# Station_lithobius_motenio_usb.net
KiCad netlist of a schematic drawn in EAGLE
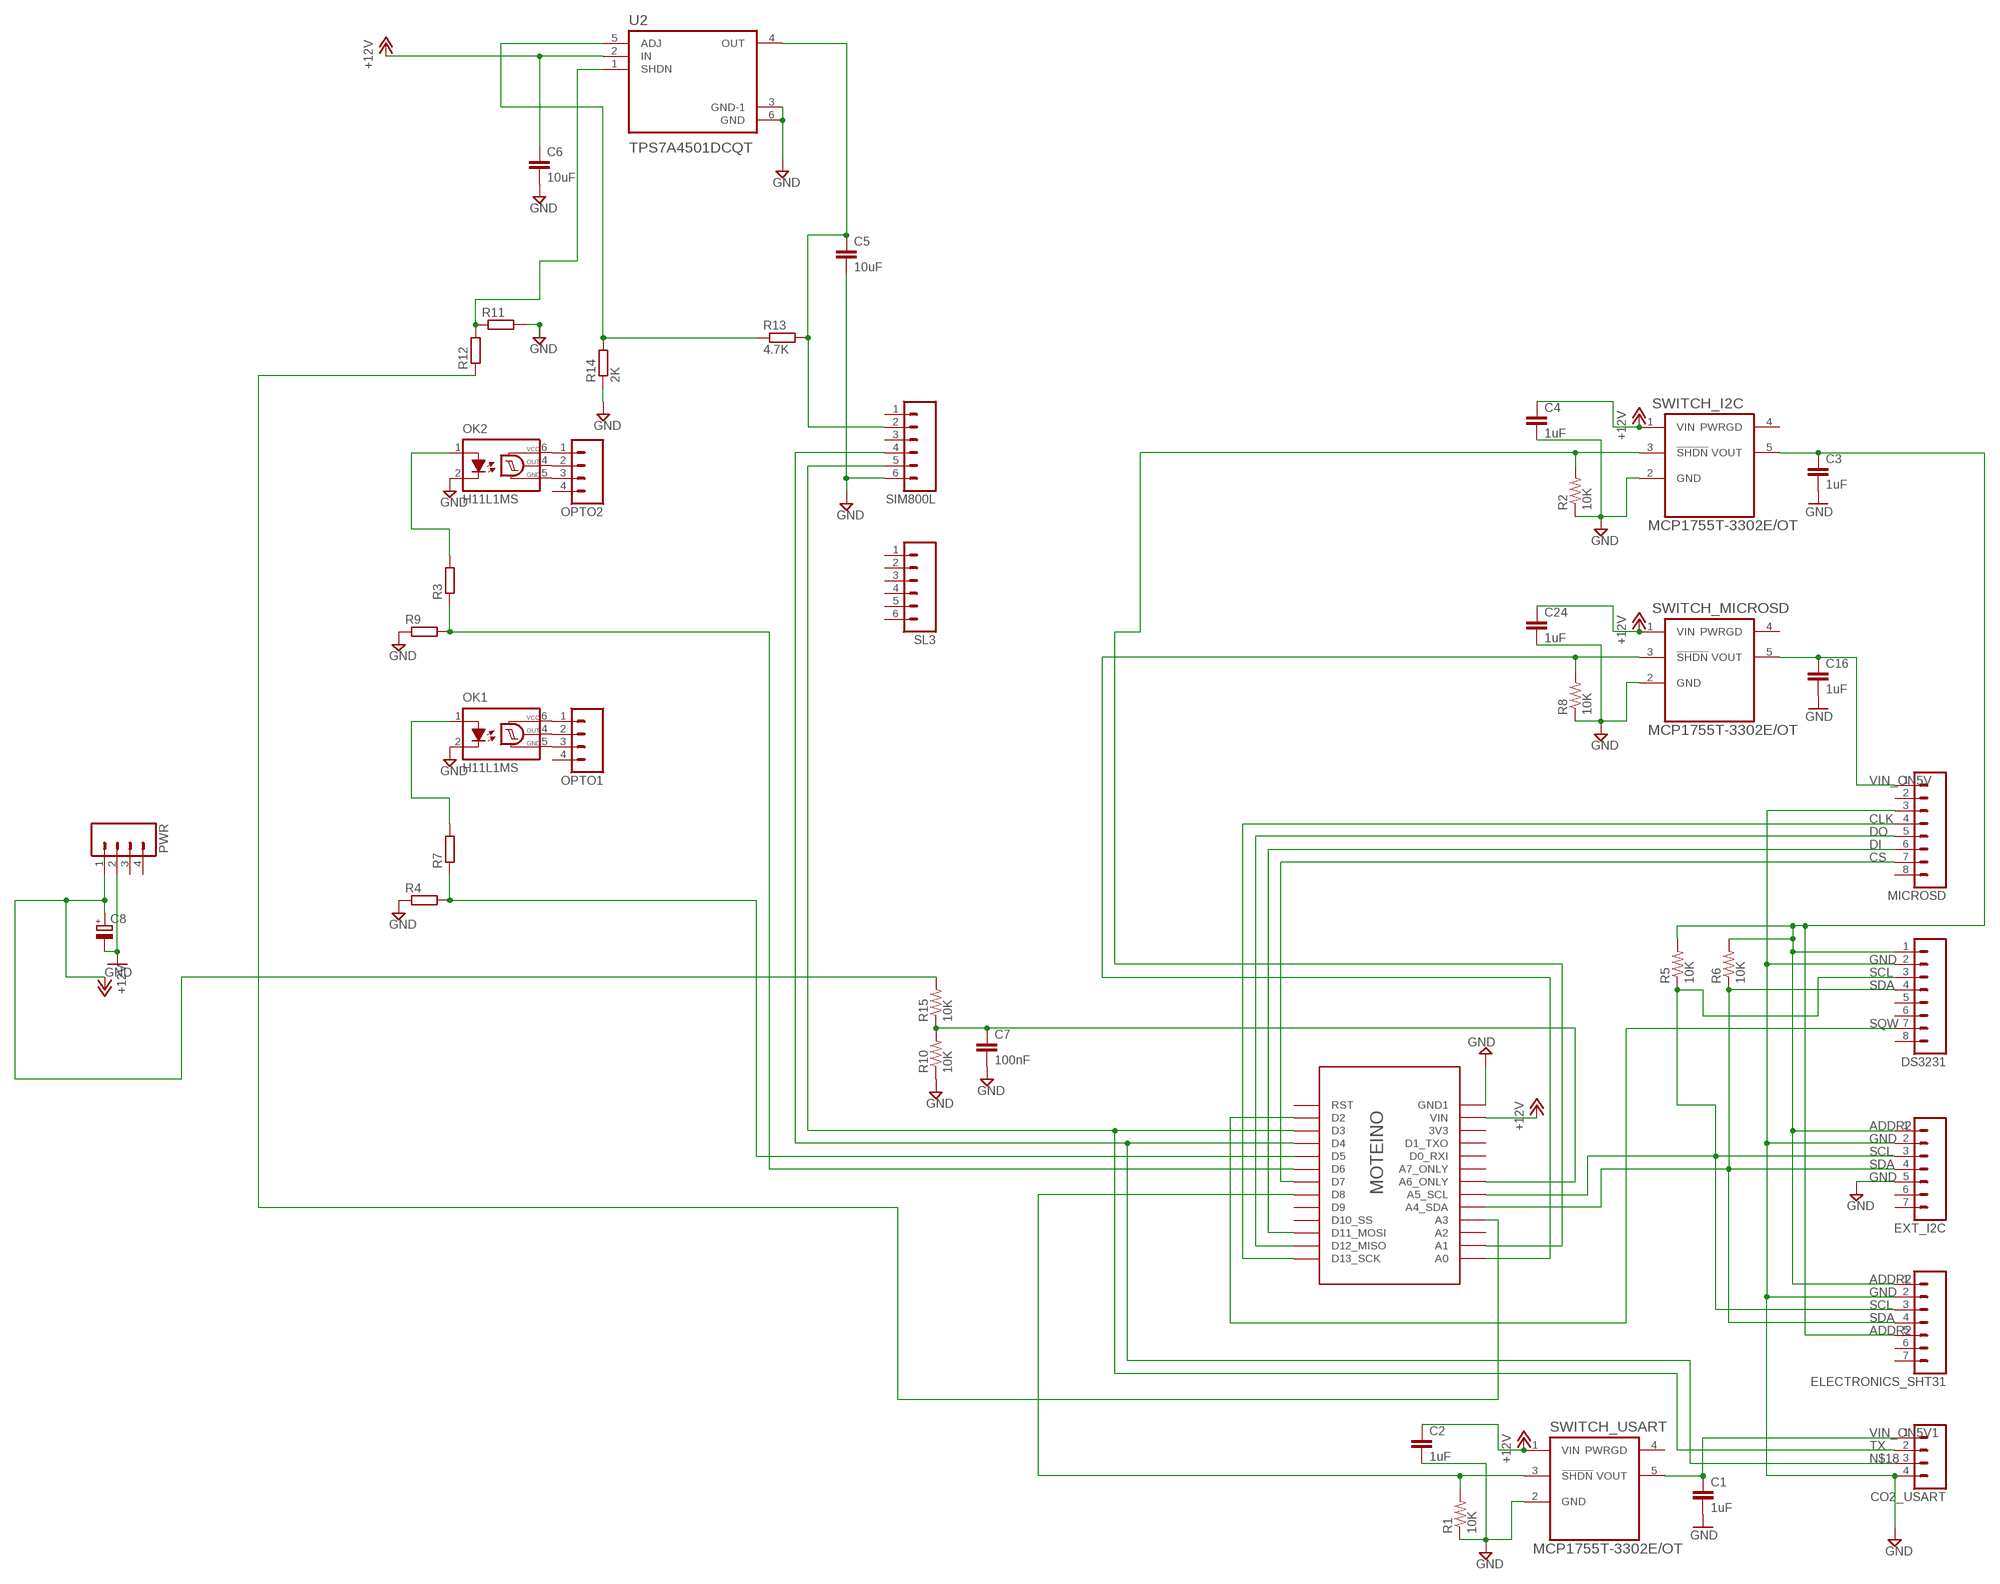
[diagram p0: schematic, sheet 1]

(export (version "E")
  (design (tool "Eeschema 10.0.6"))
  (components
    (comp (ref "C1")
      (value "1uF")
      (footprint "eagle-import:C0805K")
      (libsource (lib "eagle-import") (part "C-EUC0805K"))
    )
    (comp (ref "C2")
      (value "1uF")
      (footprint "eagle-import:C0805K")
      (libsource (lib "eagle-import") (part "C-EUC0805K"))
    )
    (comp (ref "C3")
      (value "1uF")
      (footprint "eagle-import:C0805K")
      (libsource (lib "eagle-import") (part "C-EUC0805K"))
    )
    (comp (ref "C4")
      (value "1uF")
      (footprint "eagle-import:C0805K")
      (libsource (lib "eagle-import") (part "C-EUC0805K"))
    )
    (comp (ref "C5")
      (value "10uF")
      (footprint "eagle-import:C0805K")
      (libsource (lib "eagle-import") (part "C-EUC0805K"))
    )
    (comp (ref "C6")
      (value "10uF")
      (footprint "eagle-import:C0805K")
      (libsource (lib "eagle-import") (part "C-EUC0805K"))
    )
    (comp (ref "C7")
      (value "100nF")
      (footprint "eagle-import:C0805K")
      (libsource (lib "eagle-import") (part "C-EUC0805K"))
    )
    (comp (ref "C8")
      (value "CPOL-EU153CLV-0810")
      (footprint "eagle-import:153CLV-0810")
      (libsource (lib "eagle-import") (part "CPOL-EU153CLV-0810"))
    )
    (comp (ref "C16")
      (value "1uF")
      (footprint "eagle-import:C0805K")
      (libsource (lib "eagle-import") (part "C-EUC0805K"))
    )
    (comp (ref "C24")
      (value "1uF")
      (footprint "eagle-import:C0805K")
      (libsource (lib "eagle-import") (part "C-EUC0805K"))
    )
    (comp (ref "CO2_USART")
      (value "M04")
      (footprint "eagle-import:04P")
      (libsource (lib "eagle-import") (part "M04"))
    )
    (comp (ref "DS3231")
      (value "M08")
      (footprint "eagle-import:08P")
      (libsource (lib "eagle-import") (part "M08"))
    )
    (comp (ref "ELECTRONICS_SHT31")
      (value "M07")
      (footprint "eagle-import:07P")
      (libsource (lib "eagle-import") (part "M07"))
    )
    (comp (ref "EXT_I2C")
      (value "M07")
      (footprint "eagle-import:07P")
      (libsource (lib "eagle-import") (part "M07"))
    )
    (comp (ref "MICROSD")
      (value "M08")
      (footprint "eagle-import:08P")
      (libsource (lib "eagle-import") (part "M08"))
    )
    (comp (ref "OK1")
      (value "H11L1MS")
      (footprint "eagle-import:DIL6-SMD")
      (libsource (lib "eagle-import") (part "H11LMS1"))
    )
    (comp (ref "OK2")
      (value "H11L1MS")
      (footprint "eagle-import:DIL6-SMD")
      (libsource (lib "eagle-import") (part "H11LMS1"))
    )
    (comp (ref "OPTO1")
      (value "M04")
      (footprint "eagle-import:04P")
      (libsource (lib "eagle-import") (part "M04"))
    )
    (comp (ref "OPTO2")
      (value "M04")
      (footprint "eagle-import:04P")
      (libsource (lib "eagle-import") (part "M04"))
    )
    (comp (ref "PWR")
      (value "M04")
      (footprint "eagle-import:04P")
      (libsource (lib "eagle-import") (part "M04"))
    )
    (comp (ref "R1")
      (value "10K")
      (footprint "eagle-import:R2012W")
      (libsource (lib "eagle-import") (part "R-US_R2012W"))
    )
    (comp (ref "R2")
      (value "10K")
      (footprint "eagle-import:R2012W")
      (libsource (lib "eagle-import") (part "R-US_R2012W"))
    )
    (comp (ref "R3")
      (value "R-EU_R0805")
      (footprint "eagle-import:R0805")
      (libsource (lib "eagle-import") (part "R-EU_R0805"))
    )
    (comp (ref "R4")
      (value "R-EU_R0805")
      (footprint "eagle-import:R0805")
      (libsource (lib "eagle-import") (part "R-EU_R0805"))
    )
    (comp (ref "R5")
      (value "10K")
      (footprint "eagle-import:R2012W")
      (libsource (lib "eagle-import") (part "R-US_R2012W"))
    )
    (comp (ref "R6")
      (value "10K")
      (footprint "eagle-import:R2012W")
      (libsource (lib "eagle-import") (part "R-US_R2012W"))
    )
    (comp (ref "R7")
      (value "R-EU_R0805")
      (footprint "eagle-import:R0805")
      (libsource (lib "eagle-import") (part "R-EU_R0805"))
    )
    (comp (ref "R8")
      (value "10K")
      (footprint "eagle-import:R2012W")
      (libsource (lib "eagle-import") (part "R-US_R2012W"))
    )
    (comp (ref "R9")
      (value "R-EU_R0805")
      (footprint "eagle-import:R0805")
      (libsource (lib "eagle-import") (part "R-EU_R0805"))
    )
    (comp (ref "R10")
      (value "10K")
      (footprint "eagle-import:R2012W")
      (libsource (lib "eagle-import") (part "R-US_R2012W"))
    )
    (comp (ref "R11")
      (value "R-EU_R0805")
      (footprint "eagle-import:R0805")
      (libsource (lib "eagle-import") (part "R-EU_R0805"))
    )
    (comp (ref "R12")
      (value "R-EU_R0805")
      (footprint "eagle-import:R0805")
      (libsource (lib "eagle-import") (part "R-EU_R0805"))
    )
    (comp (ref "R13")
      (value "4.7K")
      (footprint "eagle-import:R0805")
      (libsource (lib "eagle-import") (part "R-EU_R0805"))
    )
    (comp (ref "R14")
      (value "2K")
      (footprint "eagle-import:R0805")
      (libsource (lib "eagle-import") (part "R-EU_R0805"))
    )
    (comp (ref "R15")
      (value "10K")
      (footprint "eagle-import:R2012W")
      (libsource (lib "eagle-import") (part "R-US_R2012W"))
    )
    (comp (ref "SIM800L")
      (value "M06")
      (footprint "eagle-import:06P")
      (libsource (lib "eagle-import") (part "M06"))
    )
    (comp (ref "SL3")
      (value "M06")
      (footprint "eagle-import:06P")
      (libsource (lib "eagle-import") (part "M06"))
    )
    (comp (ref "SWITCH_I2C")
      (value "MCP1755T-3302E/OT")
      (footprint "eagle-import:SOT95P270X145-5N")
      (libsource (lib "eagle-import") (part "MCP1755T-3302E/OT"))
    )
    (comp (ref "SWITCH_MICROSD")
      (value "MCP1755T-3302E/OT")
      (footprint "eagle-import:SOT95P270X145-5N")
      (libsource (lib "eagle-import") (part "MCP1755T-3302E/OT"))
    )
    (comp (ref "SWITCH_USART")
      (value "MCP1755T-3302E/OT")
      (footprint "eagle-import:SOT95P270X145-5N")
      (libsource (lib "eagle-import") (part "MCP1755T-3302E/OT"))
    )
    (comp (ref "U$1")
      (value "MOTEINO_SIMPLE")
      (footprint "eagle-import:MOTEINO_SIMPLE")
      (libsource (lib "eagle-import") (part "MOTEINO_SIMPLE"))
    )
    (comp (ref "U2")
      (value "TPS7A4501DCQT")
      (footprint "eagle-import:SOT127P706X180-6N")
      (fields (field (name "MF") "Texas Instruments"))
      (libsource (lib "eagle-import") (part "TPS7A4501DCQT"))
    )
  )
  (nets
    (net (code "1") (name "+12V") (class "Default")
      (node (ref "C2") (pin "1") (pinfunction "1_1") (pintype "passive"))
      (node (ref "C24") (pin "1") (pinfunction "1_1") (pintype "passive"))
      (node (ref "C4") (pin "1") (pinfunction "1_1") (pintype "passive"))
      (node (ref "C6") (pin "1") (pinfunction "1_1") (pintype "passive"))
      (node (ref "C8") (pin "+") (pinfunction "+_+") (pintype "passive"))
      (node (ref "PWR") (pin "1") (pinfunction "1_1") (pintype "passive"))
      (node (ref "R15") (pin "2") (pinfunction "2_2") (pintype "passive"))
      (node (ref "SWITCH_I2C") (pin "1") (pinfunction "VIN_1") (pintype "power_in"))
      (node (ref "SWITCH_MICROSD") (pin "1") (pinfunction "VIN_1") (pintype "power_in"))
      (node (ref "SWITCH_USART") (pin "1") (pinfunction "VIN_1") (pintype "power_in"))
      (node (ref "U$1") (pin "VIN") (pinfunction "VIN_VIN") (pintype "bidirectional"))
      (node (ref "U2") (pin "2") (pinfunction "IN_2") (pintype "input"))
    )
    (net (code "2") (name "/ADDR2") (class "Default")
      (node (ref "C3") (pin "1") (pinfunction "1_1") (pintype "passive"))
      (node (ref "DS3231") (pin "1") (pinfunction "1_1") (pintype "passive"))
      (node (ref "ELECTRONICS_SHT31") (pin "1") (pinfunction "1_1") (pintype "passive"))
      (node (ref "ELECTRONICS_SHT31") (pin "5") (pinfunction "5_5") (pintype "passive"))
      (node (ref "EXT_I2C") (pin "1") (pinfunction "1_1") (pintype "passive"))
      (node (ref "R5") (pin "2") (pinfunction "2_2") (pintype "passive"))
      (node (ref "R6") (pin "2") (pinfunction "2_2") (pintype "passive"))
      (node (ref "SWITCH_I2C") (pin "5") (pinfunction "VOUT_5") (pintype "output"))
    )
    (net (code "3") (name "/CLK") (class "Default")
      (node (ref "MICROSD") (pin "4") (pinfunction "4_4") (pintype "passive"))
      (node (ref "U$1") (pin "D13_SCK") (pinfunction "D13_SCK_D13_SCK") (pintype "bidirectional"))
    )
    (net (code "4") (name "/CS") (class "Default")
      (node (ref "MICROSD") (pin "7") (pinfunction "7_7") (pintype "passive"))
      (node (ref "U$1") (pin "D7") (pinfunction "D7_D7") (pintype "bidirectional"))
    )
    (net (code "5") (name "/DI") (class "Default")
      (node (ref "MICROSD") (pin "6") (pinfunction "6_6") (pintype "passive"))
      (node (ref "U$1") (pin "D11_MOSI") (pinfunction "D11_MOSI_D11_MOSI") (pintype "bidirectional"))
    )
    (net (code "6") (name "/DO") (class "Default")
      (node (ref "MICROSD") (pin "5") (pinfunction "5_5") (pintype "passive"))
      (node (ref "U$1") (pin "D12_MISO") (pinfunction "D12_MISO_D12_MISO") (pintype "bidirectional"))
    )
    (net (code "7") (name "/N$18") (class "Default")
      (node (ref "CO2_USART") (pin "3") (pinfunction "3_3") (pintype "passive"))
      (node (ref "SIM800L") (pin "4") (pinfunction "4_4") (pintype "passive"))
      (node (ref "U$1") (pin "D4") (pinfunction "D4_D4") (pintype "bidirectional"))
    )
    (net (code "8") (name "/SCL") (class "Default")
      (node (ref "DS3231") (pin "3") (pinfunction "3_3") (pintype "passive"))
      (node (ref "ELECTRONICS_SHT31") (pin "3") (pinfunction "3_3") (pintype "passive"))
      (node (ref "EXT_I2C") (pin "3") (pinfunction "3_3") (pintype "passive"))
      (node (ref "R5") (pin "1") (pinfunction "1_1") (pintype "passive"))
      (node (ref "U$1") (pin "A5_SCL") (pinfunction "A5_SCL_A5_SCL") (pintype "bidirectional"))
    )
    (net (code "9") (name "/SDA") (class "Default")
      (node (ref "DS3231") (pin "4") (pinfunction "4_4") (pintype "passive"))
      (node (ref "ELECTRONICS_SHT31") (pin "4") (pinfunction "4_4") (pintype "passive"))
      (node (ref "EXT_I2C") (pin "4") (pinfunction "4_4") (pintype "passive"))
      (node (ref "R6") (pin "1") (pinfunction "1_1") (pintype "passive"))
      (node (ref "U$1") (pin "A4_SDA") (pinfunction "A4_SDA_A4_SDA") (pintype "bidirectional"))
    )
    (net (code "10") (name "/SQW") (class "Default")
      (node (ref "DS3231") (pin "7") (pinfunction "7_7") (pintype "passive"))
      (node (ref "U$1") (pin "D2") (pinfunction "D2_D2") (pintype "bidirectional"))
    )
    (net (code "11") (name "/TX") (class "Default")
      (node (ref "CO2_USART") (pin "2") (pinfunction "2_2") (pintype "passive"))
      (node (ref "SIM800L") (pin "5") (pinfunction "5_5") (pintype "passive"))
      (node (ref "U$1") (pin "D3") (pinfunction "D3_D3") (pintype "bidirectional"))
    )
    (net (code "12") (name "/VIN_ON5V") (class "Default")
      (node (ref "C16") (pin "1") (pinfunction "1_1") (pintype "passive"))
      (node (ref "MICROSD") (pin "1") (pinfunction "1_1") (pintype "passive"))
      (node (ref "SWITCH_MICROSD") (pin "5") (pinfunction "VOUT_5") (pintype "output"))
    )
    (net (code "13") (name "/VIN_ON5V1") (class "Default")
      (node (ref "C1") (pin "1") (pinfunction "1_1") (pintype "passive"))
      (node (ref "CO2_USART") (pin "1") (pinfunction "1_1") (pintype "passive"))
      (node (ref "SWITCH_USART") (pin "5") (pinfunction "VOUT_5") (pintype "output"))
    )
    (net (code "14") (name "GND") (class "Default")
      (node (ref "C1") (pin "2") (pinfunction "2_2") (pintype "passive"))
      (node (ref "C16") (pin "2") (pinfunction "2_2") (pintype "passive"))
      (node (ref "C2") (pin "2") (pinfunction "2_2") (pintype "passive"))
      (node (ref "C24") (pin "2") (pinfunction "2_2") (pintype "passive"))
      (node (ref "C3") (pin "2") (pinfunction "2_2") (pintype "passive"))
      (node (ref "C4") (pin "2") (pinfunction "2_2") (pintype "passive"))
      (node (ref "C5") (pin "2") (pinfunction "2_2") (pintype "passive"))
      (node (ref "C6") (pin "2") (pinfunction "2_2") (pintype "passive"))
      (node (ref "C7") (pin "2") (pinfunction "2_2") (pintype "passive"))
      (node (ref "C8") (pin "-") (pinfunction "-_-") (pintype "passive"))
      (node (ref "CO2_USART") (pin "4") (pinfunction "4_4") (pintype "passive"))
      (node (ref "DS3231") (pin "2") (pinfunction "2_2") (pintype "passive"))
      (node (ref "ELECTRONICS_SHT31") (pin "2") (pinfunction "2_2") (pintype "passive"))
      (node (ref "EXT_I2C") (pin "2") (pinfunction "2_2") (pintype "passive"))
      (node (ref "EXT_I2C") (pin "5") (pinfunction "5_5") (pintype "passive"))
      (node (ref "MICROSD") (pin "3") (pinfunction "3_3") (pintype "passive"))
      (node (ref "OK1") (pin "2") (pinfunction "C_2") (pintype "passive"))
      (node (ref "OK2") (pin "2") (pinfunction "C_2") (pintype "passive"))
      (node (ref "PWR") (pin "2") (pinfunction "2_2") (pintype "passive"))
      (node (ref "R1") (pin "1") (pinfunction "1_1") (pintype "passive"))
      (node (ref "R10") (pin "1") (pinfunction "1_1") (pintype "passive"))
      (node (ref "R11") (pin "2") (pinfunction "2_2") (pintype "passive"))
      (node (ref "R14") (pin "1") (pinfunction "1_1") (pintype "passive"))
      (node (ref "R2") (pin "1") (pinfunction "1_1") (pintype "passive"))
      (node (ref "R4") (pin "1") (pinfunction "1_1") (pintype "passive"))
      (node (ref "R8") (pin "1") (pinfunction "1_1") (pintype "passive"))
      (node (ref "R9") (pin "1") (pinfunction "1_1") (pintype "passive"))
      (node (ref "SIM800L") (pin "6") (pinfunction "6_6") (pintype "passive"))
      (node (ref "SWITCH_I2C") (pin "2") (pinfunction "GND_2") (pintype "passive"))
      (node (ref "SWITCH_MICROSD") (pin "2") (pinfunction "GND_2") (pintype "passive"))
      (node (ref "SWITCH_USART") (pin "2") (pinfunction "GND_2") (pintype "passive"))
      (node (ref "U$1") (pin "GND1") (pinfunction "GND1_GND1") (pintype "bidirectional"))
      (node (ref "U2") (pin "3") (pinfunction "GND-1_3") (pintype "power_in"))
      (node (ref "U2") (pin "6") (pinfunction "GND_6") (pintype "power_in"))
    )
    (net (code "15") (name "Net-(C7-Pad1)") (class "Default")
      (node (ref "C7") (pin "1") (pinfunction "1_1") (pintype "passive"))
      (node (ref "R10") (pin "2") (pinfunction "2_2") (pintype "passive"))
      (node (ref "R15") (pin "1") (pinfunction "1_1") (pintype "passive"))
      (node (ref "U$1") (pin "A6_ONLY") (pinfunction "A6_ONLY_A6_ONLY") (pintype "bidirectional"))
    )
    (net (code "16") (name "Net-(OK1-A)") (class "Default")
      (node (ref "OK1") (pin "1") (pinfunction "A_1") (pintype "passive"))
      (node (ref "R7") (pin "2") (pinfunction "2_2") (pintype "passive"))
    )
    (net (code "17") (name "Net-(OK1-GND)") (class "Default")
      (node (ref "OK1") (pin "5") (pinfunction "GND_5") (pintype "power_in"))
      (node (ref "OPTO1") (pin "3") (pinfunction "3_3") (pintype "passive"))
    )
    (net (code "18") (name "Net-(OK1-OUT)") (class "Default")
      (node (ref "OK1") (pin "4") (pinfunction "OUT_4") (pintype "output"))
      (node (ref "OPTO1") (pin "2") (pinfunction "2_2") (pintype "passive"))
    )
    (net (code "19") (name "Net-(OK1-VCC)") (class "Default")
      (node (ref "OK1") (pin "6") (pinfunction "VCC_6") (pintype "power_in"))
      (node (ref "OPTO1") (pin "1") (pinfunction "1_1") (pintype "passive"))
    )
    (net (code "20") (name "Net-(OK2-A)") (class "Default")
      (node (ref "OK2") (pin "1") (pinfunction "A_1") (pintype "passive"))
      (node (ref "R3") (pin "2") (pinfunction "2_2") (pintype "passive"))
    )
    (net (code "21") (name "Net-(OK2-GND)") (class "Default")
      (node (ref "OK2") (pin "5") (pinfunction "GND_5") (pintype "power_in"))
      (node (ref "OPTO2") (pin "3") (pinfunction "3_3") (pintype "passive"))
    )
    (net (code "22") (name "Net-(OK2-OUT)") (class "Default")
      (node (ref "OK2") (pin "4") (pinfunction "OUT_4") (pintype "output"))
      (node (ref "OPTO2") (pin "2") (pinfunction "2_2") (pintype "passive"))
    )
    (net (code "23") (name "Net-(OK2-VCC)") (class "Default")
      (node (ref "OK2") (pin "6") (pinfunction "VCC_6") (pintype "power_in"))
      (node (ref "OPTO2") (pin "1") (pinfunction "1_1") (pintype "passive"))
    )
    (net (code "24") (name "Net-(R3-Pad1)") (class "Default")
      (node (ref "R3") (pin "1") (pinfunction "1_1") (pintype "passive"))
      (node (ref "R9") (pin "2") (pinfunction "2_2") (pintype "passive"))
      (node (ref "U$1") (pin "D6") (pinfunction "D6_D6") (pintype "bidirectional"))
    )
    (net (code "25") (name "Net-(R4-Pad2)") (class "Default")
      (node (ref "R4") (pin "2") (pinfunction "2_2") (pintype "passive"))
      (node (ref "R7") (pin "1") (pinfunction "1_1") (pintype "passive"))
      (node (ref "U$1") (pin "D5") (pinfunction "D5_D5") (pintype "bidirectional"))
    )
    (net (code "26") (name "Net-(R12-Pad1)") (class "Default")
      (node (ref "R12") (pin "1") (pinfunction "1_1") (pintype "passive"))
      (node (ref "U$1") (pin "A3") (pinfunction "A3_A3") (pintype "bidirectional"))
    )
    (net (code "27") (name "Net-(SWITCH_I2C-~{SHDN})") (class "Default")
      (node (ref "R2") (pin "2") (pinfunction "2_2") (pintype "passive"))
      (node (ref "SWITCH_I2C") (pin "3") (pinfunction "~{SHDN}_3") (pintype "input"))
      (node (ref "U$1") (pin "A1") (pinfunction "A1_A1") (pintype "bidirectional"))
    )
    (net (code "28") (name "Net-(SWITCH_MICROSD-~{SHDN})") (class "Default")
      (node (ref "R8") (pin "2") (pinfunction "2_2") (pintype "passive"))
      (node (ref "SWITCH_MICROSD") (pin "3") (pinfunction "~{SHDN}_3") (pintype "input"))
      (node (ref "U$1") (pin "A0") (pinfunction "A0_A0") (pintype "bidirectional"))
    )
    (net (code "29") (name "Net-(SWITCH_USART-~{SHDN})") (class "Default")
      (node (ref "R1") (pin "2") (pinfunction "2_2") (pintype "passive"))
      (node (ref "SWITCH_USART") (pin "3") (pinfunction "~{SHDN}_3") (pintype "input"))
      (node (ref "U$1") (pin "D8") (pinfunction "D8_D8") (pintype "bidirectional"))
    )
    (net (code "30") (name "Net-(U2-ADJ)") (class "Default")
      (node (ref "R13") (pin "1") (pinfunction "1_1") (pintype "passive"))
      (node (ref "R14") (pin "2") (pinfunction "2_2") (pintype "passive"))
      (node (ref "U2") (pin "5") (pinfunction "ADJ_5") (pintype "input"))
    )
    (net (code "31") (name "Net-(U2-OUT)") (class "Default")
      (node (ref "C5") (pin "1") (pinfunction "1_1") (pintype "passive"))
      (node (ref "R13") (pin "2") (pinfunction "2_2") (pintype "passive"))
      (node (ref "SIM800L") (pin "2") (pinfunction "2_2") (pintype "passive"))
      (node (ref "U2") (pin "4") (pinfunction "OUT_4") (pintype "output"))
    )
    (net (code "32") (name "Net-(U2-SHDN)") (class "Default")
      (node (ref "R11") (pin "1") (pinfunction "1_1") (pintype "passive"))
      (node (ref "R12") (pin "2") (pinfunction "2_2") (pintype "passive"))
      (node (ref "U2") (pin "1") (pinfunction "SHDN_1") (pintype "input"))
    )
    (net (code "33") (name "unconnected-(DS3231-Pad5)") (class "Default")
      (node (ref "DS3231") (pin "5") (pinfunction "5_5") (pintype "passive"))
    )
    (net (code "34") (name "unconnected-(DS3231-Pad6)") (class "Default")
      (node (ref "DS3231") (pin "6") (pinfunction "6_6") (pintype "passive"))
    )
    (net (code "35") (name "unconnected-(DS3231-Pad8)") (class "Default")
      (node (ref "DS3231") (pin "8") (pinfunction "8_8") (pintype "passive"))
    )
    (net (code "36") (name "unconnected-(ELECTRONICS_SHT31-Pad6)") (class "Default")
      (node (ref "ELECTRONICS_SHT31") (pin "6") (pinfunction "6_6") (pintype "passive"))
    )
    (net (code "37") (name "unconnected-(ELECTRONICS_SHT31-Pad7)") (class "Default")
      (node (ref "ELECTRONICS_SHT31") (pin "7") (pinfunction "7_7") (pintype "passive"))
    )
    (net (code "38") (name "unconnected-(EXT_I2C-Pad6)") (class "Default")
      (node (ref "EXT_I2C") (pin "6") (pinfunction "6_6") (pintype "passive"))
    )
    (net (code "39") (name "unconnected-(EXT_I2C-Pad7)") (class "Default")
      (node (ref "EXT_I2C") (pin "7") (pinfunction "7_7") (pintype "passive"))
    )
    (net (code "40") (name "unconnected-(MICROSD-Pad2)") (class "Default")
      (node (ref "MICROSD") (pin "2") (pinfunction "2_2") (pintype "passive"))
    )
    (net (code "41") (name "unconnected-(MICROSD-Pad8)") (class "Default")
      (node (ref "MICROSD") (pin "8") (pinfunction "8_8") (pintype "passive"))
    )
    (net (code "42") (name "unconnected-(OPTO1-Pad4)") (class "Default")
      (node (ref "OPTO1") (pin "4") (pinfunction "4_4") (pintype "passive"))
    )
    (net (code "43") (name "unconnected-(OPTO2-Pad4)") (class "Default")
      (node (ref "OPTO2") (pin "4") (pinfunction "4_4") (pintype "passive"))
    )
    (net (code "44") (name "unconnected-(PWR-Pad3)") (class "Default")
      (node (ref "PWR") (pin "3") (pinfunction "3_3") (pintype "passive"))
    )
    (net (code "45") (name "unconnected-(PWR-Pad4)") (class "Default")
      (node (ref "PWR") (pin "4") (pinfunction "4_4") (pintype "passive"))
    )
    (net (code "46") (name "unconnected-(SIM800L-Pad1)") (class "Default")
      (node (ref "SIM800L") (pin "1") (pinfunction "1_1") (pintype "passive"))
    )
    (net (code "47") (name "unconnected-(SIM800L-Pad3)") (class "Default")
      (node (ref "SIM800L") (pin "3") (pinfunction "3_3") (pintype "passive"))
    )
    (net (code "48") (name "unconnected-(SL3-Pad1)") (class "Default")
      (node (ref "SL3") (pin "1") (pinfunction "1_1") (pintype "passive"))
    )
    (net (code "49") (name "unconnected-(SL3-Pad2)") (class "Default")
      (node (ref "SL3") (pin "2") (pinfunction "2_2") (pintype "passive"))
    )
    (net (code "50") (name "unconnected-(SL3-Pad3)") (class "Default")
      (node (ref "SL3") (pin "3") (pinfunction "3_3") (pintype "passive"))
    )
    (net (code "51") (name "unconnected-(SL3-Pad4)") (class "Default")
      (node (ref "SL3") (pin "4") (pinfunction "4_4") (pintype "passive"))
    )
    (net (code "52") (name "unconnected-(SL3-Pad5)") (class "Default")
      (node (ref "SL3") (pin "5") (pinfunction "5_5") (pintype "passive"))
    )
    (net (code "53") (name "unconnected-(SL3-Pad6)") (class "Default")
      (node (ref "SL3") (pin "6") (pinfunction "6_6") (pintype "passive"))
    )
    (net (code "54") (name "unconnected-(SWITCH_I2C-PWRGD-Pad4)") (class "Default")
      (node (ref "SWITCH_I2C") (pin "4") (pinfunction "PWRGD_4") (pintype "output"))
    )
    (net (code "55") (name "unconnected-(SWITCH_MICROSD-PWRGD-Pad4)") (class "Default")
      (node (ref "SWITCH_MICROSD") (pin "4") (pinfunction "PWRGD_4") (pintype "output"))
    )
    (net (code "56") (name "unconnected-(SWITCH_USART-PWRGD-Pad4)") (class "Default")
      (node (ref "SWITCH_USART") (pin "4") (pinfunction "PWRGD_4") (pintype "output"))
    )
    (net (code "57") (name "unconnected-(U$1-Pad3V3)") (class "Default")
      (node (ref "U$1") (pin "3V3") (pinfunction "3V3_3V3") (pintype "bidirectional"))
    )
    (net (code "58") (name "unconnected-(U$1-PadA2)") (class "Default")
      (node (ref "U$1") (pin "A2") (pinfunction "A2_A2") (pintype "bidirectional"))
    )
    (net (code "59") (name "unconnected-(U$1-PadA7_ONLY)") (class "Default")
      (node (ref "U$1") (pin "A7_ONLY") (pinfunction "A7_ONLY_A7_ONLY") (pintype "bidirectional"))
    )
    (net (code "60") (name "unconnected-(U$1-PadD0_RXI)") (class "Default")
      (node (ref "U$1") (pin "D0_RXI") (pinfunction "D0_RXI_D0_RXI") (pintype "bidirectional"))
    )
    (net (code "61") (name "unconnected-(U$1-PadD1_TXO)") (class "Default")
      (node (ref "U$1") (pin "D1_TXO") (pinfunction "D1_TXO_D1_TXO") (pintype "bidirectional"))
    )
    (net (code "62") (name "unconnected-(U$1-PadD9)") (class "Default")
      (node (ref "U$1") (pin "D9") (pinfunction "D9_D9") (pintype "bidirectional"))
    )
    (net (code "63") (name "unconnected-(U$1-PadD10_SS)") (class "Default")
      (node (ref "U$1") (pin "D10_SS") (pinfunction "D10_SS_D10_SS") (pintype "bidirectional"))
    )
    (net (code "64") (name "unconnected-(U$1-PadRST)") (class "Default")
      (node (ref "U$1") (pin "RST") (pinfunction "RST_RST") (pintype "bidirectional"))
    )
  )
)
